# emontx-shield-v1.net
KiCad netlist of a schematic drawn in EAGLE
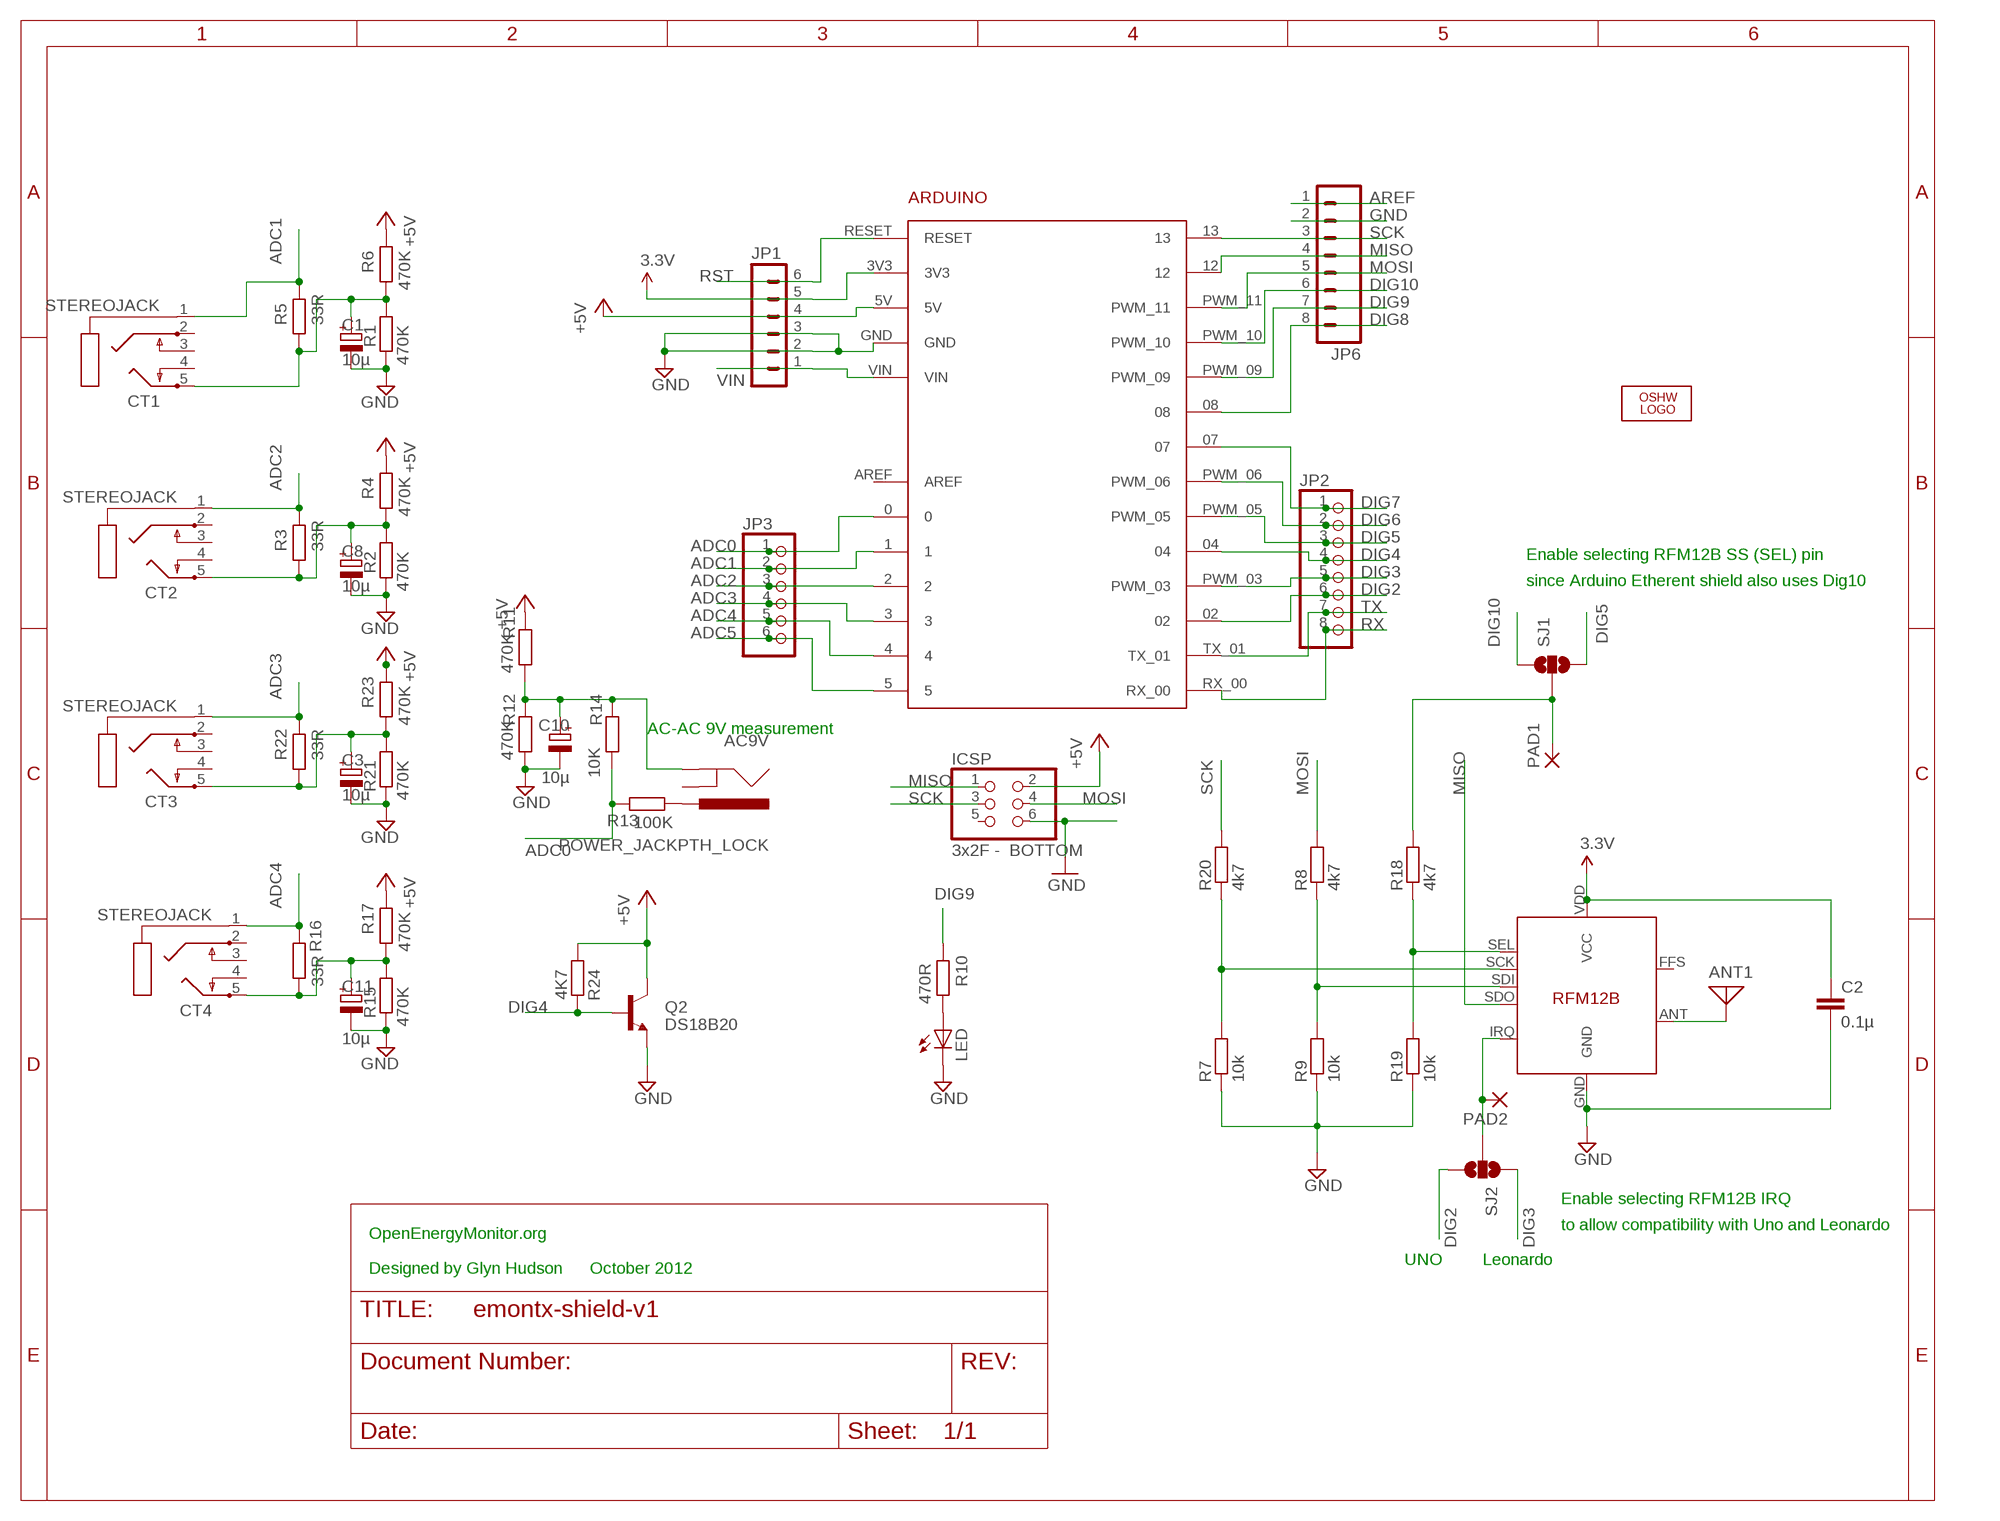
[diagram p0: schematic, sheet 1]

(export (version "E")
  (design (tool "Eeschema 10.0.6"))
  (components
    (comp (ref "AC9V")
      (value "POWER_JACKPTH_LOCK")
      (footprint "eagle-import:POWER_JACK_PTH_LOCK")
      (libsource (lib "eagle-import") (part "POWER_JACKPTH_LOCK"))
    )
    (comp (ref "ANT1")
      (value "ANTENNA")
      (footprint "eagle-import:PAD-01")
      (libsource (lib "eagle-import") (part "ANTENNA"))
    )
    (comp (ref "ARDUINO1")
      (value "ARDUINO2")
      (footprint "eagle-import:ARDUINO2")
      (libsource (lib "eagle-import") (part "ARDUINO2"))
    )
    (comp (ref "C1")
      (value "10µ")
      (footprint "eagle-import:E1,8-4")
      (libsource (lib "eagle-import") (part "CPOL-EUE1.8-4"))
    )
    (comp (ref "C2")
      (value "0.1µ")
      (footprint "eagle-import:CAP-PTH-SMALL")
      (libsource (lib "eagle-import") (part "CAPPTH"))
    )
    (comp (ref "C3")
      (value "10µ")
      (footprint "eagle-import:E1,8-4")
      (libsource (lib "eagle-import") (part "CPOL-EUE1.8-4"))
    )
    (comp (ref "C8")
      (value "10µ")
      (footprint "eagle-import:E1,8-4")
      (libsource (lib "eagle-import") (part "CPOL-EUE1.8-4"))
    )
    (comp (ref "C10")
      (value "10µ")
      (footprint "eagle-import:E1,8-4")
      (libsource (lib "eagle-import") (part "CPOL-EUE1.8-4"))
    )
    (comp (ref "C11")
      (value "10µ")
      (footprint "eagle-import:E1,8-4")
      (libsource (lib "eagle-import") (part "CPOL-EUE1.8-4"))
    )
    (comp (ref "CT1")
      (value "STEREOJACK")
      (footprint "eagle-import:STX3100")
      (libsource (lib "eagle-import") (part "STEREOJACK"))
    )
    (comp (ref "CT2")
      (value "STEREOJACK")
      (footprint "eagle-import:STX3100")
      (libsource (lib "eagle-import") (part "STEREOJACK"))
    )
    (comp (ref "CT3")
      (value "STEREOJACK")
      (footprint "eagle-import:STX3100")
      (libsource (lib "eagle-import") (part "STEREOJACK"))
    )
    (comp (ref "CT4")
      (value "STEREOJACK")
      (footprint "eagle-import:STX3100")
      (libsource (lib "eagle-import") (part "STEREOJACK"))
    )
    (comp (ref "ICSP")
      (value "3x2F - BOTTOM")
      (footprint "eagle-import:2X03")
      (libsource (lib "eagle-import") (part "PINHD-2X3"))
    )
    (comp (ref "JP1")
      (value "JEELABS_MA06-1")
      (footprint "eagle-import:JEELABS_MA06-1")
      (libsource (lib "eagle-import") (part "JEELABS_MA06-1"))
    )
    (comp (ref "JP2")
      (value "PINHD-1X8")
      (footprint "eagle-import:1X08")
      (libsource (lib "eagle-import") (part "PINHD-1X8"))
    )
    (comp (ref "JP3")
      (value "PINHD-1X6")
      (footprint "eagle-import:1X06")
      (libsource (lib "eagle-import") (part "PINHD-1X6"))
    )
    (comp (ref "JP6")
      (value "SPARKFUN_M08")
      (footprint "eagle-import:SPARKFUN_1X08")
      (libsource (lib "eagle-import") (part "SPARKFUN_M08"))
    )
    (comp (ref "LED")
      (value "LED3MM")
      (footprint "eagle-import:LED3MM")
      (libsource (lib "eagle-import") (part "LED3MM"))
    )
    (comp (ref "LOGO1")
      (value "OSHW_LOGO_10MILX0200-NT")
      (footprint "eagle-import:OSHW_10X200_NOTEXT")
      (libsource (lib "eagle-import") (part "OSHW_LOGO_10MILX0200-NT"))
    )
    (comp (ref "PAD1")
      (value "JEELABS_1,6/0,8")
      (footprint "eagle-import:JEELABS_1,6_0,8")
      (libsource (lib "eagle-import") (part "JEELABS_1,6/0,8"))
    )
    (comp (ref "PAD2")
      (value "JEELABS_1,6/0,8")
      (footprint "eagle-import:JEELABS_1,6_0,8")
      (libsource (lib "eagle-import") (part "JEELABS_1,6/0,8"))
    )
    (comp (ref "Q2")
      (value "DS18B20")
      (footprint "eagle-import:TO-92")
      (libsource (lib "eagle-import") (part "TRANSISTOR_NPNTO92"))
    )
    (comp (ref "R1")
      (value "470K")
      (footprint "eagle-import:0204_7")
      (libsource (lib "eagle-import") (part "R-EU_0204/7"))
    )
    (comp (ref "R2")
      (value "470K")
      (footprint "eagle-import:0204_7")
      (libsource (lib "eagle-import") (part "R-EU_0204/7"))
    )
    (comp (ref "R3")
      (value "33R")
      (footprint "eagle-import:0204_7")
      (libsource (lib "eagle-import") (part "R-EU_0204/7"))
    )
    (comp (ref "R4")
      (value "470K")
      (footprint "eagle-import:0204_7")
      (libsource (lib "eagle-import") (part "R-EU_0204/7"))
    )
    (comp (ref "R5")
      (value "33R")
      (footprint "eagle-import:0204_7")
      (libsource (lib "eagle-import") (part "R-EU_0204/7"))
    )
    (comp (ref "R6")
      (value "470K")
      (footprint "eagle-import:0204_7")
      (libsource (lib "eagle-import") (part "R-EU_0204/7"))
    )
    (comp (ref "R7")
      (value "10k")
      (footprint "eagle-import:RESISTOR_0204_7")
      (libsource (lib "eagle-import") (part "RESISTOR_R-EU_0204/7"))
    )
    (comp (ref "R8")
      (value "4k7")
      (footprint "eagle-import:RESISTOR_0204_7")
      (libsource (lib "eagle-import") (part "RESISTOR_R-EU_0204/7"))
    )
    (comp (ref "R9")
      (value "10k")
      (footprint "eagle-import:RESISTOR_0204_7")
      (libsource (lib "eagle-import") (part "RESISTOR_R-EU_0204/7"))
    )
    (comp (ref "R10")
      (value "470R")
      (footprint "eagle-import:0204_7")
      (libsource (lib "eagle-import") (part "R-EU_0204/7"))
    )
    (comp (ref "R11")
      (value "470K")
      (footprint "eagle-import:0204_7")
      (libsource (lib "eagle-import") (part "R-EU_0204/7"))
    )
    (comp (ref "R12")
      (value "470K")
      (footprint "eagle-import:0204_7")
      (libsource (lib "eagle-import") (part "R-EU_0204/7"))
    )
    (comp (ref "R13")
      (value "100K")
      (footprint "eagle-import:0204_7")
      (libsource (lib "eagle-import") (part "R-EU_0204/7"))
    )
    (comp (ref "R14")
      (value "10K")
      (footprint "eagle-import:0204_7")
      (libsource (lib "eagle-import") (part "R-EU_0204/7"))
    )
    (comp (ref "R15")
      (value "470K")
      (footprint "eagle-import:0204_7")
      (libsource (lib "eagle-import") (part "R-EU_0204/7"))
    )
    (comp (ref "R16")
      (value "33R")
      (footprint "eagle-import:0204_7")
      (libsource (lib "eagle-import") (part "R-EU_0204/7"))
    )
    (comp (ref "R17")
      (value "470K")
      (footprint "eagle-import:0204_7")
      (libsource (lib "eagle-import") (part "R-EU_0204/7"))
    )
    (comp (ref "R18")
      (value "4k7")
      (footprint "eagle-import:RESISTOR_0204_7")
      (libsource (lib "eagle-import") (part "RESISTOR_R-EU_0204/7"))
    )
    (comp (ref "R19")
      (value "10k")
      (footprint "eagle-import:RESISTOR_0204_7")
      (libsource (lib "eagle-import") (part "RESISTOR_R-EU_0204/7"))
    )
    (comp (ref "R20")
      (value "4k7")
      (footprint "eagle-import:RESISTOR_0204_7")
      (libsource (lib "eagle-import") (part "RESISTOR_R-EU_0204/7"))
    )
    (comp (ref "R21")
      (value "470K")
      (footprint "eagle-import:0204_7")
      (libsource (lib "eagle-import") (part "R-EU_0204/7"))
    )
    (comp (ref "R22")
      (value "33R")
      (footprint "eagle-import:0204_7")
      (libsource (lib "eagle-import") (part "R-EU_0204/7"))
    )
    (comp (ref "R23")
      (value "470K")
      (footprint "eagle-import:0204_7")
      (libsource (lib "eagle-import") (part "R-EU_0204/7"))
    )
    (comp (ref "R24")
      (value "4K7")
      (footprint "eagle-import:0204_7")
      (libsource (lib "eagle-import") (part "R-EU_0204/7"))
    )
    (comp (ref "SJ1")
      (value "SOLDERJUMPER_2WAYS")
      (footprint "eagle-import:SJ_3")
      (libsource (lib "eagle-import") (part "SOLDERJUMPER_2WAYS"))
    )
    (comp (ref "SJ2")
      (value "SOLDERJUMPER_2WAYS")
      (footprint "eagle-import:SJ_3")
      (libsource (lib "eagle-import") (part "SOLDERJUMPER_2WAYS"))
    )
    (comp (ref "U$2")
      (value "RFM12B")
      (footprint "eagle-import:RFM12B")
      (libsource (lib "eagle-import") (part "RFM12B"))
    )
  )
  (nets
    (net (code "1") (name "+5V") (class "Default")
      (node (ref "ARDUINO1") (pin "5V") (pinfunction "5V_5V") (pintype "bidirectional"))
      (node (ref "ICSP") (pin "2") (pinfunction "2_2") (pintype "passive"))
      (node (ref "JP1") (pin "4") (pinfunction "4_4") (pintype "passive"))
      (node (ref "Q2") (pin "3") (pinfunction "C_3") (pintype "passive"))
      (node (ref "R11") (pin "2") (pinfunction "2_2") (pintype "passive"))
      (node (ref "R17") (pin "2") (pinfunction "2_2") (pintype "passive"))
      (node (ref "R23") (pin "2") (pinfunction "2_2") (pintype "passive"))
      (node (ref "R24") (pin "1") (pinfunction "1_1") (pintype "passive"))
      (node (ref "R4") (pin "2") (pinfunction "2_2") (pintype "passive"))
      (node (ref "R6") (pin "2") (pinfunction "2_2") (pintype "passive"))
    )
    (net (code "2") (name "/ADC0") (class "Default")
      (node (ref "ARDUINO1") (pin "0") (pinfunction "0_0") (pintype "bidirectional"))
      (node (ref "JP3") (pin "1") (pinfunction "1_1") (pintype "passive"))
      (node (ref "R13") (pin "2") (pinfunction "2_2") (pintype "passive"))
      (node (ref "R14") (pin "1") (pinfunction "1_1") (pintype "passive"))
    )
    (net (code "3") (name "/ADC1") (class "Default")
      (node (ref "ARDUINO1") (pin "1") (pinfunction "1_1") (pintype "bidirectional"))
      (node (ref "CT1") (pin "1") (pinfunction "1_1") (pintype "passive"))
      (node (ref "JP3") (pin "2") (pinfunction "2_2") (pintype "passive"))
      (node (ref "R5") (pin "2") (pinfunction "2_2") (pintype "passive"))
    )
    (net (code "4") (name "/ADC2") (class "Default")
      (node (ref "ARDUINO1") (pin "2") (pinfunction "2_2") (pintype "bidirectional"))
      (node (ref "CT2") (pin "1") (pinfunction "1_1") (pintype "passive"))
      (node (ref "JP3") (pin "3") (pinfunction "3_3") (pintype "passive"))
      (node (ref "R3") (pin "2") (pinfunction "2_2") (pintype "passive"))
    )
    (net (code "5") (name "/ADC3") (class "Default")
      (node (ref "ARDUINO1") (pin "3") (pinfunction "3_3") (pintype "bidirectional"))
      (node (ref "CT3") (pin "1") (pinfunction "1_1") (pintype "passive"))
      (node (ref "JP3") (pin "4") (pinfunction "4_4") (pintype "passive"))
      (node (ref "R22") (pin "2") (pinfunction "2_2") (pintype "passive"))
    )
    (net (code "6") (name "/ADC4") (class "Default")
      (node (ref "ARDUINO1") (pin "4") (pinfunction "4_4") (pintype "bidirectional"))
      (node (ref "CT4") (pin "1") (pinfunction "1_1") (pintype "passive"))
      (node (ref "JP3") (pin "5") (pinfunction "5_5") (pintype "passive"))
      (node (ref "R16") (pin "2") (pinfunction "2_2") (pintype "passive"))
    )
    (net (code "7") (name "/ADC5") (class "Default")
      (node (ref "ARDUINO1") (pin "5") (pinfunction "5_5") (pintype "bidirectional"))
      (node (ref "JP3") (pin "6") (pinfunction "6_6") (pintype "passive"))
    )
    (net (code "8") (name "/AREF") (class "Default")
      (node (ref "JP6") (pin "1") (pinfunction "1_1") (pintype "passive"))
    )
    (net (code "9") (name "/DIG2") (class "Default")
      (node (ref "ARDUINO1") (pin "02") (pinfunction "02_02") (pintype "bidirectional"))
      (node (ref "JP2") (pin "6") (pinfunction "6_6") (pintype "passive"))
      (node (ref "SJ2") (pin "3") (pinfunction "3_3") (pintype "passive"))
    )
    (net (code "10") (name "/DIG3") (class "Default")
      (node (ref "ARDUINO1") (pin "PWM_03") (pinfunction "PWM_03_PWM_03") (pintype "bidirectional"))
      (node (ref "JP2") (pin "5") (pinfunction "5_5") (pintype "passive"))
      (node (ref "SJ2") (pin "1") (pinfunction "1_1") (pintype "passive"))
    )
    (net (code "11") (name "/DIG4") (class "Default")
      (node (ref "ARDUINO1") (pin "04") (pinfunction "04_04") (pintype "bidirectional"))
      (node (ref "JP2") (pin "4") (pinfunction "4_4") (pintype "passive"))
      (node (ref "Q2") (pin "2") (pinfunction "B_2") (pintype "passive"))
      (node (ref "R24") (pin "2") (pinfunction "2_2") (pintype "passive"))
    )
    (net (code "12") (name "/DIG5") (class "Default")
      (node (ref "ARDUINO1") (pin "PWM_05") (pinfunction "PWM_05_PWM_05") (pintype "bidirectional"))
      (node (ref "JP2") (pin "3") (pinfunction "3_3") (pintype "passive"))
      (node (ref "SJ1") (pin "3") (pinfunction "3_3") (pintype "passive"))
    )
    (net (code "13") (name "/DIG6") (class "Default")
      (node (ref "ARDUINO1") (pin "PWM_06") (pinfunction "PWM_06_PWM_06") (pintype "bidirectional"))
      (node (ref "JP2") (pin "2") (pinfunction "2_2") (pintype "passive"))
    )
    (net (code "14") (name "/DIG7") (class "Default")
      (node (ref "ARDUINO1") (pin "07") (pinfunction "07_07") (pintype "bidirectional"))
      (node (ref "JP2") (pin "1") (pinfunction "1_1") (pintype "passive"))
    )
    (net (code "15") (name "/DIG8") (class "Default")
      (node (ref "ARDUINO1") (pin "08") (pinfunction "08_08") (pintype "bidirectional"))
      (node (ref "JP6") (pin "8") (pinfunction "8_8") (pintype "passive"))
    )
    (net (code "16") (name "/DIG9") (class "Default")
      (node (ref "ARDUINO1") (pin "PWM_09") (pinfunction "PWM_09_PWM_09") (pintype "bidirectional"))
      (node (ref "JP6") (pin "7") (pinfunction "7_7") (pintype "passive"))
      (node (ref "R10") (pin "2") (pinfunction "2_2") (pintype "passive"))
    )
    (net (code "17") (name "/DIG10") (class "Default")
      (node (ref "ARDUINO1") (pin "PWM_10") (pinfunction "PWM_10_PWM_10") (pintype "bidirectional"))
      (node (ref "JP6") (pin "6") (pinfunction "6_6") (pintype "passive"))
      (node (ref "SJ1") (pin "1") (pinfunction "1_1") (pintype "passive"))
    )
    (net (code "18") (name "/MISO") (class "Default")
      (node (ref "ARDUINO1") (pin "12") (pinfunction "12_12") (pintype "bidirectional"))
      (node (ref "ICSP") (pin "1") (pinfunction "1_1") (pintype "passive"))
      (node (ref "JP6") (pin "4") (pinfunction "4_4") (pintype "passive"))
      (node (ref "U$2") (pin "SDO") (pinfunction "SDO_SDO") (pintype "output"))
    )
    (net (code "19") (name "/MOSI") (class "Default")
      (node (ref "ARDUINO1") (pin "PWM_11") (pinfunction "PWM_11_PWM_11") (pintype "bidirectional"))
      (node (ref "ICSP") (pin "4") (pinfunction "4_4") (pintype "passive"))
      (node (ref "JP6") (pin "5") (pinfunction "5_5") (pintype "passive"))
      (node (ref "R8") (pin "2") (pinfunction "2_2") (pintype "passive"))
    )
    (net (code "20") (name "/RST") (class "Default")
      (node (ref "ARDUINO1") (pin "RESET") (pinfunction "RESET_RESET") (pintype "bidirectional"))
      (node (ref "JP1") (pin "6") (pinfunction "6_6") (pintype "passive"))
    )
    (net (code "21") (name "/RX") (class "Default")
      (node (ref "ARDUINO1") (pin "RX_00") (pinfunction "RX_00_RX_00") (pintype "bidirectional"))
      (node (ref "JP2") (pin "8") (pinfunction "8_8") (pintype "passive"))
    )
    (net (code "22") (name "/SCK") (class "Default")
      (node (ref "ARDUINO1") (pin "13") (pinfunction "13_13") (pintype "bidirectional"))
      (node (ref "ICSP") (pin "3") (pinfunction "3_3") (pintype "passive"))
      (node (ref "JP6") (pin "3") (pinfunction "3_3") (pintype "passive"))
      (node (ref "R20") (pin "2") (pinfunction "2_2") (pintype "passive"))
    )
    (net (code "23") (name "/TX") (class "Default")
      (node (ref "ARDUINO1") (pin "TX_01") (pinfunction "TX_01_TX_01") (pintype "bidirectional"))
      (node (ref "JP2") (pin "7") (pinfunction "7_7") (pintype "passive"))
    )
    (net (code "24") (name "/VIN") (class "Default")
      (node (ref "ARDUINO1") (pin "VIN") (pinfunction "VIN_VIN") (pintype "bidirectional"))
      (node (ref "JP1") (pin "1") (pinfunction "1_1") (pintype "passive"))
    )
    (net (code "25") (name "3.3V") (class "Default")
      (node (ref "ARDUINO1") (pin "3V3") (pinfunction "3V3_3V3") (pintype "bidirectional"))
      (node (ref "C2") (pin "1") (pinfunction "1_1") (pintype "passive"))
      (node (ref "JP1") (pin "5") (pinfunction "5_5") (pintype "passive"))
      (node (ref "U$2") (pin "VDD") (pinfunction "VCC_VDD") (pintype "power_in"))
    )
    (net (code "26") (name "GND") (class "Default")
      (node (ref "ARDUINO1") (pin "GND") (pinfunction "GND_GND") (pintype "bidirectional"))
      (node (ref "C1") (pin "-") (pinfunction "-_-") (pintype "passive"))
      (node (ref "C10") (pin "-") (pinfunction "-_-") (pintype "passive"))
      (node (ref "C11") (pin "-") (pinfunction "-_-") (pintype "passive"))
      (node (ref "C2") (pin "2") (pinfunction "2_2") (pintype "passive"))
      (node (ref "C3") (pin "-") (pinfunction "-_-") (pintype "passive"))
      (node (ref "C8") (pin "-") (pinfunction "-_-") (pintype "passive"))
      (node (ref "ICSP") (pin "6") (pinfunction "6_6") (pintype "passive"))
      (node (ref "JP1") (pin "2") (pinfunction "2_2") (pintype "passive"))
      (node (ref "JP1") (pin "3") (pinfunction "3_3") (pintype "passive"))
      (node (ref "JP6") (pin "2") (pinfunction "2_2") (pintype "passive"))
      (node (ref "LED") (pin "K") (pinfunction "C_K") (pintype "passive"))
      (node (ref "Q2") (pin "1") (pinfunction "E_1") (pintype "passive"))
      (node (ref "R1") (pin "2") (pinfunction "2_2") (pintype "passive"))
      (node (ref "R12") (pin "1") (pinfunction "1_1") (pintype "passive"))
      (node (ref "R15") (pin "2") (pinfunction "2_2") (pintype "passive"))
      (node (ref "R19") (pin "1") (pinfunction "1_1") (pintype "passive"))
      (node (ref "R2") (pin "2") (pinfunction "2_2") (pintype "passive"))
      (node (ref "R21") (pin "2") (pinfunction "2_2") (pintype "passive"))
      (node (ref "R7") (pin "1") (pinfunction "1_1") (pintype "passive"))
      (node (ref "R9") (pin "1") (pinfunction "1_1") (pintype "passive"))
      (node (ref "U$2") (pin "GND") (pinfunction "GND_GND") (pintype "power_in"))
    )
    (net (code "27") (name "Net-(AC9V-PadGND)") (class "Default")
      (node (ref "AC9V") (pin "GND") (pinfunction "GND_GND") (pintype "bidirectional"))
      (node (ref "C10") (pin "+") (pinfunction "+_+") (pintype "passive"))
      (node (ref "R11") (pin "1") (pinfunction "1_1") (pintype "passive"))
      (node (ref "R12") (pin "2") (pinfunction "2_2") (pintype "passive"))
      (node (ref "R14") (pin "2") (pinfunction "2_2") (pintype "passive"))
    )
    (net (code "28") (name "Net-(AC9V-PadPWR)") (class "Default")
      (node (ref "AC9V") (pin "PWR") (pinfunction "PWR_PWR") (pintype "bidirectional"))
      (node (ref "R13") (pin "1") (pinfunction "1_1") (pintype "passive"))
    )
    (net (code "29") (name "Net-(ANT1-Pad1)") (class "Default")
      (node (ref "ANT1") (pin "1") (pinfunction "1_1") (pintype "output"))
      (node (ref "U$2") (pin "ANT") (pinfunction "ANT_ANT") (pintype "passive"))
    )
    (net (code "30") (name "Net-(C1-Pad+)") (class "Default")
      (node (ref "C1") (pin "+") (pinfunction "+_+") (pintype "passive"))
      (node (ref "CT1") (pin "5") (pinfunction "5_5") (pintype "passive"))
      (node (ref "R1") (pin "1") (pinfunction "1_1") (pintype "passive"))
      (node (ref "R5") (pin "1") (pinfunction "1_1") (pintype "passive"))
      (node (ref "R6") (pin "1") (pinfunction "1_1") (pintype "passive"))
    )
    (net (code "31") (name "Net-(C3-Pad+)") (class "Default")
      (node (ref "C3") (pin "+") (pinfunction "+_+") (pintype "passive"))
      (node (ref "CT3") (pin "5") (pinfunction "5_5") (pintype "passive"))
      (node (ref "R21") (pin "1") (pinfunction "1_1") (pintype "passive"))
      (node (ref "R22") (pin "1") (pinfunction "1_1") (pintype "passive"))
      (node (ref "R23") (pin "1") (pinfunction "1_1") (pintype "passive"))
    )
    (net (code "32") (name "Net-(C8-Pad+)") (class "Default")
      (node (ref "C8") (pin "+") (pinfunction "+_+") (pintype "passive"))
      (node (ref "CT2") (pin "5") (pinfunction "5_5") (pintype "passive"))
      (node (ref "R2") (pin "1") (pinfunction "1_1") (pintype "passive"))
      (node (ref "R3") (pin "1") (pinfunction "1_1") (pintype "passive"))
      (node (ref "R4") (pin "1") (pinfunction "1_1") (pintype "passive"))
    )
    (net (code "33") (name "Net-(C11-Pad+)") (class "Default")
      (node (ref "C11") (pin "+") (pinfunction "+_+") (pintype "passive"))
      (node (ref "CT4") (pin "5") (pinfunction "5_5") (pintype "passive"))
      (node (ref "R15") (pin "1") (pinfunction "1_1") (pintype "passive"))
      (node (ref "R16") (pin "1") (pinfunction "1_1") (pintype "passive"))
      (node (ref "R17") (pin "1") (pinfunction "1_1") (pintype "passive"))
    )
    (net (code "34") (name "Net-(LED-PadA)") (class "Default")
      (node (ref "LED") (pin "A") (pinfunction "A_A") (pintype "passive"))
      (node (ref "R10") (pin "1") (pinfunction "1_1") (pintype "passive"))
    )
    (net (code "35") (name "Net-(PAD1-P)") (class "Default")
      (node (ref "PAD1") (pin "1") (pinfunction "P_1") (pintype "passive"))
      (node (ref "R18") (pin "2") (pinfunction "2_2") (pintype "passive"))
      (node (ref "SJ1") (pin "2") (pinfunction "2_2") (pintype "passive"))
    )
    (net (code "36") (name "Net-(PAD2-P)") (class "Default")
      (node (ref "PAD2") (pin "1") (pinfunction "P_1") (pintype "passive"))
      (node (ref "SJ2") (pin "2") (pinfunction "2_2") (pintype "passive"))
      (node (ref "U$2") (pin "IRQ") (pinfunction "IRQ_IRQ") (pintype "open_collector"))
    )
    (net (code "37") (name "Net-(R8-Pad1)") (class "Default")
      (node (ref "R8") (pin "1") (pinfunction "1_1") (pintype "passive"))
      (node (ref "R9") (pin "2") (pinfunction "2_2") (pintype "passive"))
      (node (ref "U$2") (pin "SDI") (pinfunction "SDI_SDI") (pintype "input"))
    )
    (net (code "38") (name "Net-(R18-Pad1)") (class "Default")
      (node (ref "R18") (pin "1") (pinfunction "1_1") (pintype "passive"))
      (node (ref "R19") (pin "2") (pinfunction "2_2") (pintype "passive"))
      (node (ref "U$2") (pin "SEL") (pinfunction "SEL_SEL") (pintype "input"))
    )
    (net (code "39") (name "Net-(R20-Pad1)") (class "Default")
      (node (ref "R20") (pin "1") (pinfunction "1_1") (pintype "passive"))
      (node (ref "R7") (pin "2") (pinfunction "2_2") (pintype "passive"))
      (node (ref "U$2") (pin "SCK") (pinfunction "SCK_SCK") (pintype "input"))
    )
    (net (code "40") (name "unconnected-(AC9V-PadGNDBREAK)") (class "Default")
      (node (ref "AC9V") (pin "GNDBREAK") (pinfunction "GNDBREAK_GNDBREAK") (pintype "bidirectional"))
    )
    (net (code "41") (name "unconnected-(ARDUINO1-PadAREF)") (class "Default")
      (node (ref "ARDUINO1") (pin "AREF") (pinfunction "AREF_AREF") (pintype "bidirectional"))
    )
    (net (code "42") (name "unconnected-(CT1-Pad2)") (class "Default")
      (node (ref "CT1") (pin "2") (pinfunction "2_2") (pintype "passive"))
    )
    (net (code "43") (name "unconnected-(CT1-Pad3)") (class "Default")
      (node (ref "CT1") (pin "3") (pinfunction "3_3") (pintype "passive"))
    )
    (net (code "44") (name "unconnected-(CT1-Pad4)") (class "Default")
      (node (ref "CT1") (pin "4") (pinfunction "4_4") (pintype "passive"))
    )
    (net (code "45") (name "unconnected-(CT2-Pad2)") (class "Default")
      (node (ref "CT2") (pin "2") (pinfunction "2_2") (pintype "passive"))
    )
    (net (code "46") (name "unconnected-(CT2-Pad3)") (class "Default")
      (node (ref "CT2") (pin "3") (pinfunction "3_3") (pintype "passive"))
    )
    (net (code "47") (name "unconnected-(CT2-Pad4)") (class "Default")
      (node (ref "CT2") (pin "4") (pinfunction "4_4") (pintype "passive"))
    )
    (net (code "48") (name "unconnected-(CT3-Pad2)") (class "Default")
      (node (ref "CT3") (pin "2") (pinfunction "2_2") (pintype "passive"))
    )
    (net (code "49") (name "unconnected-(CT3-Pad3)") (class "Default")
      (node (ref "CT3") (pin "3") (pinfunction "3_3") (pintype "passive"))
    )
    (net (code "50") (name "unconnected-(CT3-Pad4)") (class "Default")
      (node (ref "CT3") (pin "4") (pinfunction "4_4") (pintype "passive"))
    )
    (net (code "51") (name "unconnected-(CT4-Pad2)") (class "Default")
      (node (ref "CT4") (pin "2") (pinfunction "2_2") (pintype "passive"))
    )
    (net (code "52") (name "unconnected-(CT4-Pad3)") (class "Default")
      (node (ref "CT4") (pin "3") (pinfunction "3_3") (pintype "passive"))
    )
    (net (code "53") (name "unconnected-(CT4-Pad4)") (class "Default")
      (node (ref "CT4") (pin "4") (pinfunction "4_4") (pintype "passive"))
    )
    (net (code "54") (name "unconnected-(ICSP-Pad5)") (class "Default")
      (node (ref "ICSP") (pin "5") (pinfunction "5_5") (pintype "passive"))
    )
    (net (code "55") (name "unconnected-(U$2-PadFFS)") (class "Default")
      (node (ref "U$2") (pin "FFS") (pinfunction "FFS_FFS") (pintype "bidirectional"))
    )
  )
)
